# Processor.net
KiCad netlist of a schematic drawn in Altium Designer
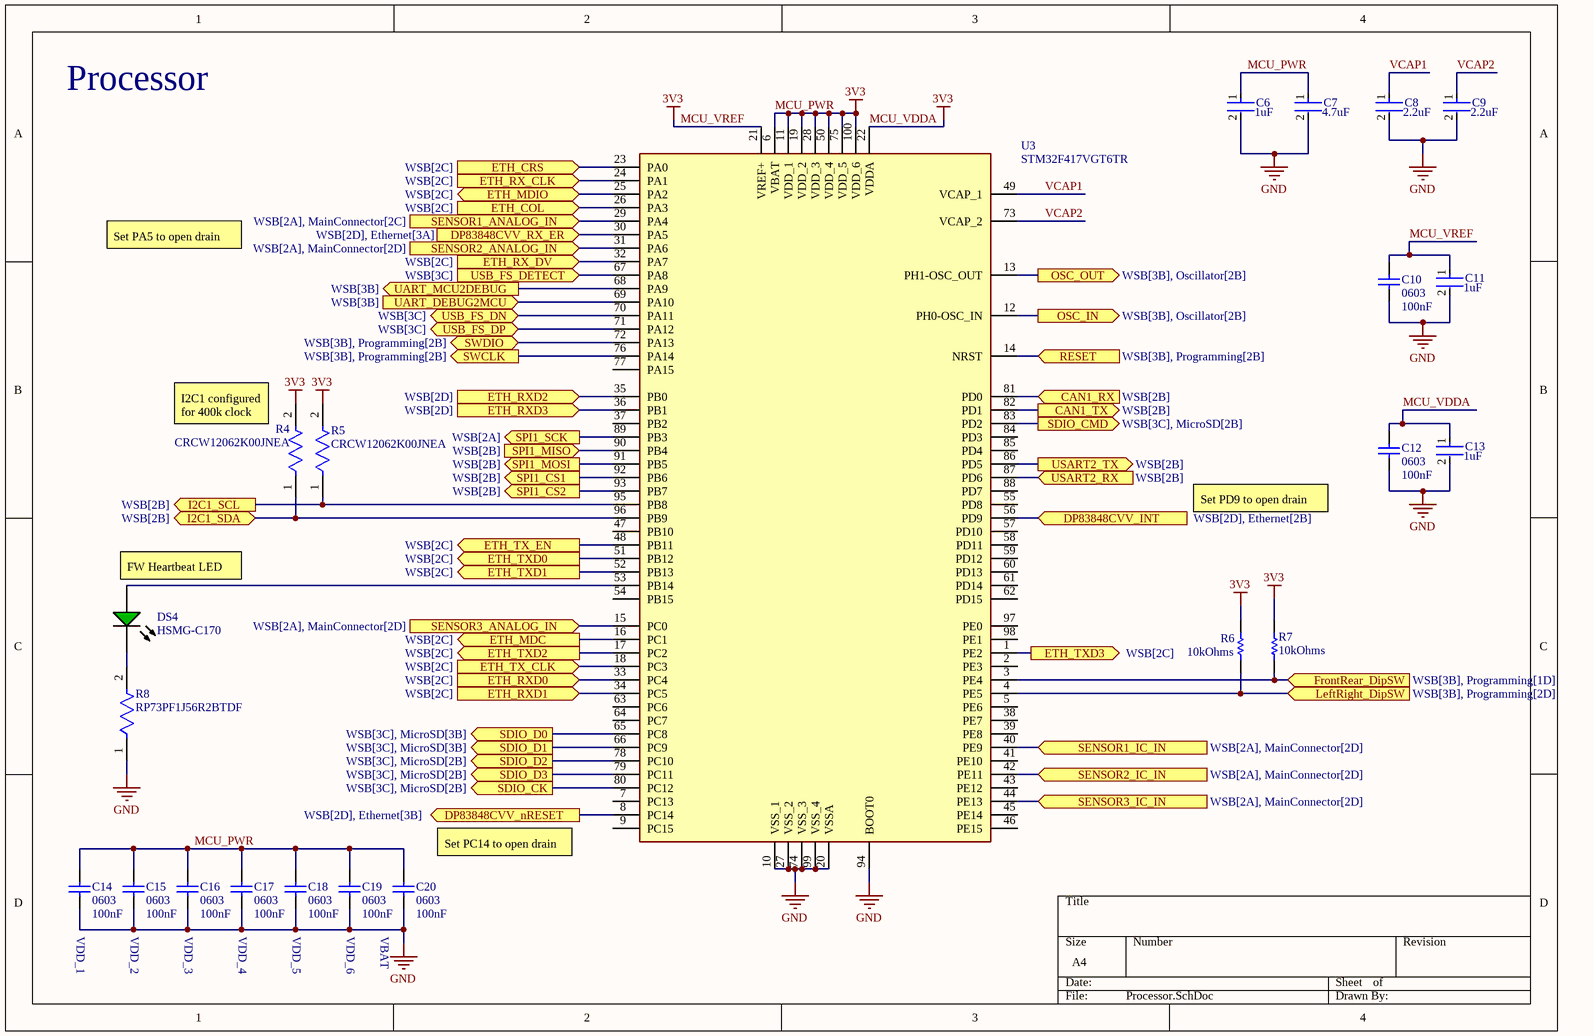
[diagram p0: Processor.SchDoc]

(export (version "E")
  (design (tool "Eeschema 10.0.6"))
  (components
    (comp (ref "C6")
      (value "CL10A105KA8NNNC")
      (footprint "FP-CL10-IPC_C")
      (description "Cap Ceramic 1uF 25V X5R ±10% Pad SMD 0603 +85°C T/R")
      (fields
        (field (name "CAPACITANCE") "1uF")
        (field (name "VOLTAGE") "25V")
        (field (name "TOLERANCE") "10%")
      )
      (libsource (lib "Altium Content Vault") (part "b4654b650e69147ec39a6b967a45e02"))
    )
    (comp (ref "C7")
      (value "C1005X5R1A475K050BC")
      (footprint "FP-C1005-050-0_15-MFG")
      (description "CAP CER 4.7UF 10V X5R 0402")
      (fields (field (name "TOLERANCE") "10%") (field (name "CAPACITANCE") "4.7uF"))
      (libsource (lib "Altium Content Vault") (part "b4654b650e69147ec39a6b967a45e02"))
    )
    (comp (ref "C8")
      (value "C0603C225K4PACTU")
      (footprint "FP-C0603C225K4PACTU-MFG")
      (description "CAP CER 2.2UF 16V X5R 0603")
      (fields
        (field (name "CAPACITANCE") "2.2uF")
        (field (name "TOLERANCE") "10%")
        (field (name "VOLTAGE") "16V")
      )
      (libsource (lib "Altium Content Vault") (part "b4654b650e69147ec39a6b967a45e02"))
    )
    (comp (ref "C9")
      (value "C0603C225K4PACTU")
      (footprint "FP-C0603C225K4PACTU-MFG")
      (description "CAP CER 2.2UF 16V X5R 0603")
      (fields
        (field (name "CAPACITANCE") "2.2uF")
        (field (name "TOLERANCE") "10%")
        (field (name "VOLTAGE") "16V")
      )
      (libsource (lib "Altium Content Vault") (part "b4654b650e69147ec39a6b967a45e02"))
    )
    (comp (ref "C10")
      (value "C0603X104K5RACTU")
      (footprint "CAPC1608X87X35NL15T15")
      (fields
        (field (name "MANUFACTURER") "Kemet")
        (field (name "CASE CODE (IMPERIAL)") "0603")
        (field (name "CAPACITANCE") "100nF")
        (field (name "TOLERANCE") "10%")
        (field (name "VOLTAGE") "50V")
      )
      (libsource (lib "Altium Content Vault") (part "CAP"))
    )
    (comp (ref "C11")
      (value "CL10A105KA8NNNC")
      (footprint "FP-CL10-IPC_C")
      (description "Cap Ceramic 1uF 25V X5R ±10% Pad SMD 0603 +85°C T/R")
      (fields
        (field (name "CAPACITANCE") "1uF")
        (field (name "VOLTAGE") "25V")
        (field (name "TOLERANCE") "10%")
      )
      (libsource (lib "Altium Content Vault") (part "b4654b650e69147ec39a6b967a45e02"))
    )
    (comp (ref "C12")
      (value "C0603X104K5RACTU")
      (footprint "CAPC1608X87X35NL15T15")
      (fields
        (field (name "MANUFACTURER") "Kemet")
        (field (name "CASE CODE (IMPERIAL)") "0603")
        (field (name "CAPACITANCE") "100nF")
        (field (name "TOLERANCE") "10%")
        (field (name "VOLTAGE") "50V")
      )
      (libsource (lib "Altium Content Vault") (part "CAP"))
    )
    (comp (ref "C13")
      (value "CL10A105KA8NNNC")
      (footprint "FP-CL10-IPC_C")
      (description "Cap Ceramic 1uF 25V X5R ±10% Pad SMD 0603 +85°C T/R")
      (fields
        (field (name "CAPACITANCE") "1uF")
        (field (name "VOLTAGE") "25V")
        (field (name "TOLERANCE") "10%")
      )
      (libsource (lib "Altium Content Vault") (part "b4654b650e69147ec39a6b967a45e02"))
    )
    (comp (ref "C14")
      (value "C0603X104K5RACTU")
      (footprint "CAPC1608X87X35NL15T15")
      (fields
        (field (name "MANUFACTURER") "Kemet")
        (field (name "CASE CODE (IMPERIAL)") "0603")
        (field (name "CAPACITANCE") "100nF")
        (field (name "TOLERANCE") "10%")
        (field (name "VOLTAGE") "50V")
      )
      (libsource (lib "Altium Content Vault") (part "CAP"))
    )
    (comp (ref "C15")
      (value "C0603X104K5RACTU")
      (footprint "CAPC1608X87X35NL15T15")
      (fields
        (field (name "MANUFACTURER") "Kemet")
        (field (name "CASE CODE (IMPERIAL)") "0603")
        (field (name "CAPACITANCE") "100nF")
        (field (name "TOLERANCE") "10%")
        (field (name "VOLTAGE") "50V")
      )
      (libsource (lib "Altium Content Vault") (part "CAP"))
    )
    (comp (ref "C16")
      (value "C0603X104K5RACTU")
      (footprint "CAPC1608X87X35NL15T15")
      (fields
        (field (name "MANUFACTURER") "Kemet")
        (field (name "CASE CODE (IMPERIAL)") "0603")
        (field (name "CAPACITANCE") "100nF")
        (field (name "TOLERANCE") "10%")
        (field (name "VOLTAGE") "50V")
      )
      (libsource (lib "Altium Content Vault") (part "CAP"))
    )
    (comp (ref "C17")
      (value "C0603X104K5RACTU")
      (footprint "CAPC1608X87X35NL15T15")
      (fields
        (field (name "MANUFACTURER") "Kemet")
        (field (name "CASE CODE (IMPERIAL)") "0603")
        (field (name "CAPACITANCE") "100nF")
        (field (name "TOLERANCE") "10%")
        (field (name "VOLTAGE") "50V")
      )
      (libsource (lib "Altium Content Vault") (part "CAP"))
    )
    (comp (ref "C18")
      (value "C0603X104K5RACTU")
      (footprint "CAPC1608X87X35NL15T15")
      (fields
        (field (name "MANUFACTURER") "Kemet")
        (field (name "CASE CODE (IMPERIAL)") "0603")
        (field (name "CAPACITANCE") "100nF")
        (field (name "TOLERANCE") "10%")
        (field (name "VOLTAGE") "50V")
      )
      (libsource (lib "Altium Content Vault") (part "CAP"))
    )
    (comp (ref "C19")
      (value "C0603X104K5RACTU")
      (footprint "CAPC1608X87X35NL15T15")
      (fields
        (field (name "MANUFACTURER") "Kemet")
        (field (name "CASE CODE (IMPERIAL)") "0603")
        (field (name "CAPACITANCE") "100nF")
        (field (name "TOLERANCE") "10%")
        (field (name "VOLTAGE") "50V")
      )
      (libsource (lib "Altium Content Vault") (part "CAP"))
    )
    (comp (ref "C20")
      (value "C0603X104K5RACTU")
      (footprint "CAPC1608X87X35NL15T15")
      (fields
        (field (name "MANUFACTURER") "Kemet")
        (field (name "CASE CODE (IMPERIAL)") "0603")
        (field (name "CAPACITANCE") "100nF")
        (field (name "TOLERANCE") "10%")
        (field (name "VOLTAGE") "50V")
      )
      (libsource (lib "Altium Content Vault") (part "CAP"))
    )
    (comp (ref "DS4")
      (value "HSMG-C170")
      (footprint "AVAG-HSMX-C170_V")
      (description "Chip LED, Green, 2.2 V, -40 to 85 degC, 2-Pin SMD, Pb-Free, Tape and Reel")
      (fields (field (name "MANUFACTURER") "Avago"))
      (libsource (lib "Altium Content Vault") (part "LED_GREEN_A1K2-2"))
    )
    (comp (ref "R4")
      (value "CRCW12062K00JNEA")
      (footprint "FP-CRCW1206-e3-IPC_B")
      (description "RES Thick Film, 2kΩ, 5%, 0.25W, 200ppm/°C, 1206")
      (fields (field (name "TOLERANCE") "5%"))
      (libsource (lib "Altium Content Vault") (part "1029c3af85768c4190bb7ad29bc67b5"))
    )
    (comp (ref "R5")
      (value "CRCW12062K00JNEA")
      (footprint "FP-CRCW1206-e3-IPC_B")
      (description "RES Thick Film, 2kΩ, 5%, 0.25W, 200ppm/°C, 1206")
      (fields (field (name "TOLERANCE") "5%"))
      (libsource (lib "Altium Content Vault") (part "1029c3af85768c4190bb7ad29bc67b5"))
    )
    (comp (ref "R6")
      (value "RC0603JR-0710KL")
      (footprint "RESC1608X55X25ML10T15")
      (description "Resistor, 10 KOhm, +/- 5%, 100 mW, -55 to 155 degC, 0603 (1608 Metric), RoHS, Tape and Reel")
      (fields
        (field (name "RESISTANCE") "10kOhms")
        (field (name "MANUFACTURER") "Yageo")
        (field (name "TOLERANCE") "5%")
      )
      (libsource (lib "Altium Content Vault") (part "RES-2"))
    )
    (comp (ref "R7")
      (value "RC0603JR-0710KL")
      (footprint "RESC1608X55X25ML10T15")
      (description "Resistor, 10 KOhm, +/- 5%, 100 mW, -55 to 155 degC, 0603 (1608 Metric), RoHS, Tape and Reel")
      (fields
        (field (name "RESISTANCE") "10kOhms")
        (field (name "MANUFACTURER") "Yageo")
        (field (name "TOLERANCE") "5%")
      )
      (libsource (lib "Altium Content Vault") (part "RES-2"))
    )
    (comp (ref "R8")
      (value "RP73PF1J56R2BTDF")
      (footprint "FP-RP73P-1J-MFG")
      (description "RES SMD 56.2 OHM 0.1% 1/6W 0603")
      (fields
        (field (name "OCTOPART") "https://octopart.com/rp73pf1j56r2btdf-te+connectivity-45466141")
        (field (name "TOLERANCE") "0.001")
      )
      (libsource (lib "Altium Content Vault") (part "1029c3af85768c4190bb7ad29bc67b5"))
    )
    (comp (ref "U3")
      (value "STM32F417VGT6TR")
      (footprint "STM-LQFP100_N")
      (description "RISC Microcontroller, 32-Bit, FLASH, CORTEX-M4 CPU, 168MHz, CMOS, PQFP100")
      (fields (field (name "MANUFACTURER") "STMicroelectronics"))
      (libsource (lib "Microcontrollers") (part "STM32F417VGT6TR"))
    )
  )
  (nets
    (net (code "1") (name "/CAN1_RX") (class "Default")
      (node (ref "U3") (pin "81") (pinfunction "PD0_81") (pintype "passive"))
    )
    (net (code "2") (name "/CAN1_TX") (class "Default")
      (node (ref "U3") (pin "82") (pinfunction "PD1_82") (pintype "passive"))
    )
    (net (code "3") (name "/DP83848CVV_INT") (class "Default")
      (node (ref "U3") (pin "56") (pinfunction "PD9_56") (pintype "passive"))
    )
    (net (code "4") (name "/DP83848CVV_RX_ER") (class "Default")
      (node (ref "U3") (pin "30") (pinfunction "PA5_30") (pintype "passive"))
    )
    (net (code "5") (name "/DP83848CVV_nRESET") (class "Default")
      (node (ref "U3") (pin "8") (pinfunction "PC14_8") (pintype "passive"))
    )
    (net (code "6") (name "/ETH_COL") (class "Default")
      (node (ref "U3") (pin "26") (pinfunction "PA3_26") (pintype "passive"))
    )
    (net (code "7") (name "/ETH_CRS") (class "Default")
      (node (ref "U3") (pin "23") (pinfunction "PA0_23") (pintype "passive"))
    )
    (net (code "8") (name "/ETH_MDC") (class "Default")
      (node (ref "U3") (pin "16") (pinfunction "PC1_16") (pintype "passive"))
    )
    (net (code "9") (name "/ETH_MDIO") (class "Default")
      (node (ref "U3") (pin "25") (pinfunction "PA2_25") (pintype "passive"))
    )
    (net (code "10") (name "/ETH_RXD0") (class "Default")
      (node (ref "U3") (pin "33") (pinfunction "PC4_33") (pintype "passive"))
    )
    (net (code "11") (name "/ETH_RXD1") (class "Default")
      (node (ref "U3") (pin "34") (pinfunction "PC5_34") (pintype "passive"))
    )
    (net (code "12") (name "/ETH_RXD2") (class "Default")
      (node (ref "U3") (pin "35") (pinfunction "PB0_35") (pintype "passive"))
    )
    (net (code "13") (name "/ETH_RXD3") (class "Default")
      (node (ref "U3") (pin "36") (pinfunction "PB1_36") (pintype "passive"))
    )
    (net (code "14") (name "/ETH_RX_CLK") (class "Default")
      (node (ref "U3") (pin "24") (pinfunction "PA1_24") (pintype "passive"))
    )
    (net (code "15") (name "/ETH_RX_DV") (class "Default")
      (node (ref "U3") (pin "32") (pinfunction "PA7_32") (pintype "passive"))
    )
    (net (code "16") (name "/ETH_TXD0") (class "Default")
      (node (ref "U3") (pin "51") (pinfunction "PB12_51") (pintype "passive"))
    )
    (net (code "17") (name "/ETH_TXD1") (class "Default")
      (node (ref "U3") (pin "52") (pinfunction "PB13_52") (pintype "passive"))
    )
    (net (code "18") (name "/ETH_TXD2") (class "Default")
      (node (ref "U3") (pin "17") (pinfunction "PC2_17") (pintype "passive"))
    )
    (net (code "19") (name "/ETH_TXD3") (class "Default")
      (node (ref "U3") (pin "1") (pinfunction "PE2_1") (pintype "passive"))
    )
    (net (code "20") (name "/ETH_TX_CLK") (class "Default")
      (node (ref "U3") (pin "18") (pinfunction "PC3_18") (pintype "passive"))
    )
    (net (code "21") (name "/ETH_TX_EN") (class "Default")
      (node (ref "U3") (pin "48") (pinfunction "PB11_48") (pintype "passive"))
    )
    (net (code "22") (name "/FrontRear_DipSW") (class "Default")
      (node (ref "R7") (pin "1") (pinfunction "1_1") (pintype "passive"))
      (node (ref "U3") (pin "3") (pinfunction "PE4_3") (pintype "passive"))
    )
    (net (code "23") (name "/I2C1_SCL") (class "Default")
      (node (ref "R5") (pin "1") (pinfunction "1_1") (pintype "passive"))
      (node (ref "U3") (pin "95") (pinfunction "PB8_95") (pintype "passive"))
    )
    (net (code "24") (name "/I2C1_SDA") (class "Default")
      (node (ref "R4") (pin "1") (pinfunction "1_1") (pintype "passive"))
      (node (ref "U3") (pin "96") (pinfunction "PB9_96") (pintype "passive"))
    )
    (net (code "25") (name "/LeftRight_DipSW") (class "Default")
      (node (ref "R6") (pin "1") (pinfunction "1_1") (pintype "passive"))
      (node (ref "U3") (pin "4") (pinfunction "PE5_4") (pintype "passive"))
    )
    (net (code "26") (name "/OSC_IN") (class "Default")
      (node (ref "U3") (pin "12") (pinfunction "PH0-OSC_IN_12") (pintype "passive"))
    )
    (net (code "27") (name "/OSC_OUT") (class "Default")
      (node (ref "U3") (pin "13") (pinfunction "PH1-OSC_OUT_13") (pintype "passive"))
    )
    (net (code "28") (name "/RESET") (class "Default")
      (node (ref "U3") (pin "14") (pinfunction "NRST_14") (pintype "passive"))
    )
    (net (code "29") (name "/SDIO_CK") (class "Default")
      (node (ref "U3") (pin "80") (pinfunction "PC12_80") (pintype "passive"))
    )
    (net (code "30") (name "/SDIO_CMD") (class "Default")
      (node (ref "U3") (pin "83") (pinfunction "PD2_83") (pintype "passive"))
    )
    (net (code "31") (name "/SDIO_D0") (class "Default")
      (node (ref "U3") (pin "65") (pinfunction "PC8_65") (pintype "passive"))
    )
    (net (code "32") (name "/SDIO_D1") (class "Default")
      (node (ref "U3") (pin "66") (pinfunction "PC9_66") (pintype "passive"))
    )
    (net (code "33") (name "/SDIO_D2") (class "Default")
      (node (ref "U3") (pin "78") (pinfunction "PC10_78") (pintype "passive"))
    )
    (net (code "34") (name "/SDIO_D3") (class "Default")
      (node (ref "U3") (pin "79") (pinfunction "PC11_79") (pintype "passive"))
    )
    (net (code "35") (name "/SENSOR1_ANALOG_IN") (class "Default")
      (node (ref "U3") (pin "29") (pinfunction "PA4_29") (pintype "passive"))
    )
    (net (code "36") (name "/SENSOR1_IC_IN") (class "Default")
      (node (ref "U3") (pin "40") (pinfunction "PE9_40") (pintype "passive"))
    )
    (net (code "37") (name "/SENSOR2_ANALOG_IN") (class "Default")
      (node (ref "U3") (pin "31") (pinfunction "PA6_31") (pintype "passive"))
    )
    (net (code "38") (name "/SENSOR2_IC_IN") (class "Default")
      (node (ref "U3") (pin "42") (pinfunction "PE11_42") (pintype "passive"))
    )
    (net (code "39") (name "/SENSOR3_ANALOG_IN") (class "Default")
      (node (ref "U3") (pin "15") (pinfunction "PC0_15") (pintype "passive"))
    )
    (net (code "40") (name "/SENSOR3_IC_IN") (class "Default")
      (node (ref "U3") (pin "44") (pinfunction "PE13_44") (pintype "passive"))
    )
    (net (code "41") (name "/SPI1_CS1") (class "Default")
      (node (ref "U3") (pin "92") (pinfunction "PB6_92") (pintype "passive"))
    )
    (net (code "42") (name "/SPI1_CS2") (class "Default")
      (node (ref "U3") (pin "93") (pinfunction "PB7_93") (pintype "passive"))
    )
    (net (code "43") (name "/SPI1_MISO") (class "Default")
      (node (ref "U3") (pin "90") (pinfunction "PB4_90") (pintype "passive"))
    )
    (net (code "44") (name "/SPI1_MOSI") (class "Default")
      (node (ref "U3") (pin "91") (pinfunction "PB5_91") (pintype "passive"))
    )
    (net (code "45") (name "/SPI1_SCK") (class "Default")
      (node (ref "U3") (pin "89") (pinfunction "PB3_89") (pintype "passive"))
    )
    (net (code "46") (name "/SWCLK") (class "Default")
      (node (ref "U3") (pin "76") (pinfunction "PA14_76") (pintype "passive"))
    )
    (net (code "47") (name "/SWDIO") (class "Default")
      (node (ref "U3") (pin "72") (pinfunction "PA13_72") (pintype "passive"))
    )
    (net (code "48") (name "/UART_DEBUG2MCU") (class "Default")
      (node (ref "U3") (pin "69") (pinfunction "PA10_69") (pintype "passive"))
    )
    (net (code "49") (name "/UART_MCU2DEBUG") (class "Default")
      (node (ref "U3") (pin "68") (pinfunction "PA9_68") (pintype "passive"))
    )
    (net (code "50") (name "/USART2_RX") (class "Default")
      (node (ref "U3") (pin "87") (pinfunction "PD6_87") (pintype "passive"))
    )
    (net (code "51") (name "/USART2_TX") (class "Default")
      (node (ref "U3") (pin "86") (pinfunction "PD5_86") (pintype "passive"))
    )
    (net (code "52") (name "/USB_FS_DETECT") (class "Default")
      (node (ref "U3") (pin "67") (pinfunction "PA8_67") (pintype "passive"))
    )
    (net (code "53") (name "/USB_FS_DN") (class "Default")
      (node (ref "U3") (pin "70") (pinfunction "PA11_70") (pintype "passive"))
    )
    (net (code "54") (name "/USB_FS_DP") (class "Default")
      (node (ref "U3") (pin "71") (pinfunction "PA12_71") (pintype "passive"))
    )
    (net (code "55") (name "/VCAP1") (class "Default")
      (node (ref "C8") (pin "1") (pinfunction "1_1") (pintype "passive"))
      (node (ref "U3") (pin "49") (pinfunction "VCAP_1_49") (pintype "passive"))
    )
    (net (code "56") (name "/VCAP2") (class "Default")
      (node (ref "C9") (pin "1") (pinfunction "1_1") (pintype "passive"))
      (node (ref "U3") (pin "73") (pinfunction "VCAP_2_73") (pintype "passive"))
    )
    (net (code "57") (name "3V3") (class "Default")
      (node (ref "C10") (pin "1") (pinfunction "1_1") (pintype "passive"))
      (node (ref "C11") (pin "1") (pinfunction "1_1") (pintype "passive"))
      (node (ref "C12") (pin "1") (pinfunction "1_1") (pintype "passive"))
      (node (ref "C13") (pin "1") (pinfunction "1_1") (pintype "passive"))
      (node (ref "C14") (pin "2") (pinfunction "2_2") (pintype "passive"))
      (node (ref "C15") (pin "2") (pinfunction "2_2") (pintype "passive"))
      (node (ref "C16") (pin "2") (pinfunction "2_2") (pintype "passive"))
      (node (ref "C17") (pin "2") (pinfunction "2_2") (pintype "passive"))
      (node (ref "C18") (pin "2") (pinfunction "2_2") (pintype "passive"))
      (node (ref "C19") (pin "2") (pinfunction "2_2") (pintype "passive"))
      (node (ref "C20") (pin "2") (pinfunction "2_2") (pintype "passive"))
      (node (ref "C6") (pin "1") (pinfunction "1_1") (pintype "passive"))
      (node (ref "C7") (pin "1") (pinfunction "1_1") (pintype "passive"))
      (node (ref "R4") (pin "2") (pinfunction "2_2") (pintype "passive"))
      (node (ref "R5") (pin "2") (pinfunction "2_2") (pintype "passive"))
      (node (ref "R6") (pin "2") (pinfunction "2_2") (pintype "passive"))
      (node (ref "R7") (pin "2") (pinfunction "2_2") (pintype "passive"))
      (node (ref "U3") (pin "100") (pinfunction "VDD_6_100") (pintype "passive"))
      (node (ref "U3") (pin "11") (pinfunction "VDD_1_11") (pintype "passive"))
      (node (ref "U3") (pin "19") (pinfunction "VDD_2_19") (pintype "passive"))
      (node (ref "U3") (pin "21") (pinfunction "VREF+_21") (pintype "passive"))
      (node (ref "U3") (pin "22") (pinfunction "VDDA_22") (pintype "passive"))
      (node (ref "U3") (pin "28") (pinfunction "VDD_3_28") (pintype "passive"))
      (node (ref "U3") (pin "50") (pinfunction "VDD_4_50") (pintype "passive"))
      (node (ref "U3") (pin "6") (pinfunction "VBAT_6") (pintype "passive"))
      (node (ref "U3") (pin "75") (pinfunction "VDD_5_75") (pintype "passive"))
    )
    (net (code "58") (name "GND") (class "Default")
      (node (ref "C10") (pin "2") (pinfunction "2_2") (pintype "passive"))
      (node (ref "C11") (pin "2") (pinfunction "2_2") (pintype "passive"))
      (node (ref "C12") (pin "2") (pinfunction "2_2") (pintype "passive"))
      (node (ref "C13") (pin "2") (pinfunction "2_2") (pintype "passive"))
      (node (ref "C14") (pin "1") (pinfunction "1_1") (pintype "passive"))
      (node (ref "C15") (pin "1") (pinfunction "1_1") (pintype "passive"))
      (node (ref "C16") (pin "1") (pinfunction "1_1") (pintype "passive"))
      (node (ref "C17") (pin "1") (pinfunction "1_1") (pintype "passive"))
      (node (ref "C18") (pin "1") (pinfunction "1_1") (pintype "passive"))
      (node (ref "C19") (pin "1") (pinfunction "1_1") (pintype "passive"))
      (node (ref "C20") (pin "1") (pinfunction "1_1") (pintype "passive"))
      (node (ref "C6") (pin "2") (pinfunction "2_2") (pintype "passive"))
      (node (ref "C7") (pin "2") (pinfunction "2_2") (pintype "passive"))
      (node (ref "C8") (pin "2") (pinfunction "2_2") (pintype "passive"))
      (node (ref "C9") (pin "2") (pinfunction "2_2") (pintype "passive"))
      (node (ref "R8") (pin "1") (pinfunction "1_1") (pintype "passive"))
      (node (ref "U3") (pin "10") (pinfunction "VSS_1_10") (pintype "passive"))
      (node (ref "U3") (pin "20") (pinfunction "VSSA_20") (pintype "passive"))
      (node (ref "U3") (pin "27") (pinfunction "VSS_2_27") (pintype "passive"))
      (node (ref "U3") (pin "74") (pinfunction "VSS_3_74") (pintype "passive"))
      (node (ref "U3") (pin "94") (pinfunction "BOOT0_94") (pintype "passive"))
      (node (ref "U3") (pin "99") (pinfunction "VSS_4_99") (pintype "passive"))
    )
    (net (code "59") (name "Net-(DS4-A)") (class "Default")
      (node (ref "DS4") (pin "1") (pinfunction "A_1") (pintype "passive"))
      (node (ref "U3") (pin "53") (pinfunction "PB14_53") (pintype "passive"))
    )
    (net (code "60") (name "Net-(DS4-K)") (class "Default")
      (node (ref "DS4") (pin "2") (pinfunction "K_2") (pintype "passive"))
      (node (ref "R8") (pin "2") (pinfunction "2_2") (pintype "passive"))
    )
    (net (code "61") (name "unconnected-(U3-PA15-Pad77)") (class "Default")
      (node (ref "U3") (pin "77") (pinfunction "PA15_77") (pintype "passive"))
    )
    (net (code "62") (name "unconnected-(U3-PB2-Pad37)") (class "Default")
      (node (ref "U3") (pin "37") (pinfunction "PB2_37") (pintype "passive"))
    )
    (net (code "63") (name "unconnected-(U3-PB10-Pad47)") (class "Default")
      (node (ref "U3") (pin "47") (pinfunction "PB10_47") (pintype "passive"))
    )
    (net (code "64") (name "unconnected-(U3-PB15-Pad54)") (class "Default")
      (node (ref "U3") (pin "54") (pinfunction "PB15_54") (pintype "passive"))
    )
    (net (code "65") (name "unconnected-(U3-PC6-Pad63)") (class "Default")
      (node (ref "U3") (pin "63") (pinfunction "PC6_63") (pintype "passive"))
    )
    (net (code "66") (name "unconnected-(U3-PC7-Pad64)") (class "Default")
      (node (ref "U3") (pin "64") (pinfunction "PC7_64") (pintype "passive"))
    )
    (net (code "67") (name "unconnected-(U3-PC13-Pad7)") (class "Default")
      (node (ref "U3") (pin "7") (pinfunction "PC13_7") (pintype "passive"))
    )
    (net (code "68") (name "unconnected-(U3-PC15-Pad9)") (class "Default")
      (node (ref "U3") (pin "9") (pinfunction "PC15_9") (pintype "passive"))
    )
    (net (code "69") (name "unconnected-(U3-PD3-Pad84)") (class "Default")
      (node (ref "U3") (pin "84") (pinfunction "PD3_84") (pintype "passive"))
    )
    (net (code "70") (name "unconnected-(U3-PD4-Pad85)") (class "Default")
      (node (ref "U3") (pin "85") (pinfunction "PD4_85") (pintype "passive"))
    )
    (net (code "71") (name "unconnected-(U3-PD7-Pad88)") (class "Default")
      (node (ref "U3") (pin "88") (pinfunction "PD7_88") (pintype "passive"))
    )
    (net (code "72") (name "unconnected-(U3-PD8-Pad55)") (class "Default")
      (node (ref "U3") (pin "55") (pinfunction "PD8_55") (pintype "passive"))
    )
    (net (code "73") (name "unconnected-(U3-PD10-Pad57)") (class "Default")
      (node (ref "U3") (pin "57") (pinfunction "PD10_57") (pintype "passive"))
    )
    (net (code "74") (name "unconnected-(U3-PD11-Pad58)") (class "Default")
      (node (ref "U3") (pin "58") (pinfunction "PD11_58") (pintype "passive"))
    )
    (net (code "75") (name "unconnected-(U3-PD12-Pad59)") (class "Default")
      (node (ref "U3") (pin "59") (pinfunction "PD12_59") (pintype "passive"))
    )
    (net (code "76") (name "unconnected-(U3-PD13-Pad60)") (class "Default")
      (node (ref "U3") (pin "60") (pinfunction "PD13_60") (pintype "passive"))
    )
    (net (code "77") (name "unconnected-(U3-PD14-Pad61)") (class "Default")
      (node (ref "U3") (pin "61") (pinfunction "PD14_61") (pintype "passive"))
    )
    (net (code "78") (name "unconnected-(U3-PD15-Pad62)") (class "Default")
      (node (ref "U3") (pin "62") (pinfunction "PD15_62") (pintype "passive"))
    )
    (net (code "79") (name "unconnected-(U3-PE0-Pad97)") (class "Default")
      (node (ref "U3") (pin "97") (pinfunction "PE0_97") (pintype "passive"))
    )
    (net (code "80") (name "unconnected-(U3-PE1-Pad98)") (class "Default")
      (node (ref "U3") (pin "98") (pinfunction "PE1_98") (pintype "passive"))
    )
    (net (code "81") (name "unconnected-(U3-PE3-Pad2)") (class "Default")
      (node (ref "U3") (pin "2") (pinfunction "PE3_2") (pintype "passive"))
    )
    (net (code "82") (name "unconnected-(U3-PE6-Pad5)") (class "Default")
      (node (ref "U3") (pin "5") (pinfunction "PE6_5") (pintype "passive"))
    )
    (net (code "83") (name "unconnected-(U3-PE7-Pad38)") (class "Default")
      (node (ref "U3") (pin "38") (pinfunction "PE7_38") (pintype "passive"))
    )
    (net (code "84") (name "unconnected-(U3-PE8-Pad39)") (class "Default")
      (node (ref "U3") (pin "39") (pinfunction "PE8_39") (pintype "passive"))
    )
    (net (code "85") (name "unconnected-(U3-PE10-Pad41)") (class "Default")
      (node (ref "U3") (pin "41") (pinfunction "PE10_41") (pintype "passive"))
    )
    (net (code "86") (name "unconnected-(U3-PE12-Pad43)") (class "Default")
      (node (ref "U3") (pin "43") (pinfunction "PE12_43") (pintype "passive"))
    )
    (net (code "87") (name "unconnected-(U3-PE14-Pad45)") (class "Default")
      (node (ref "U3") (pin "45") (pinfunction "PE14_45") (pintype "passive"))
    )
    (net (code "88") (name "unconnected-(U3-PE15-Pad46)") (class "Default")
      (node (ref "U3") (pin "46") (pinfunction "PE15_46") (pintype "passive"))
    )
  )
)
